# IOTB_EDGE_V3_0.net
KiCad netlist of a schematic drawn in EAGLE
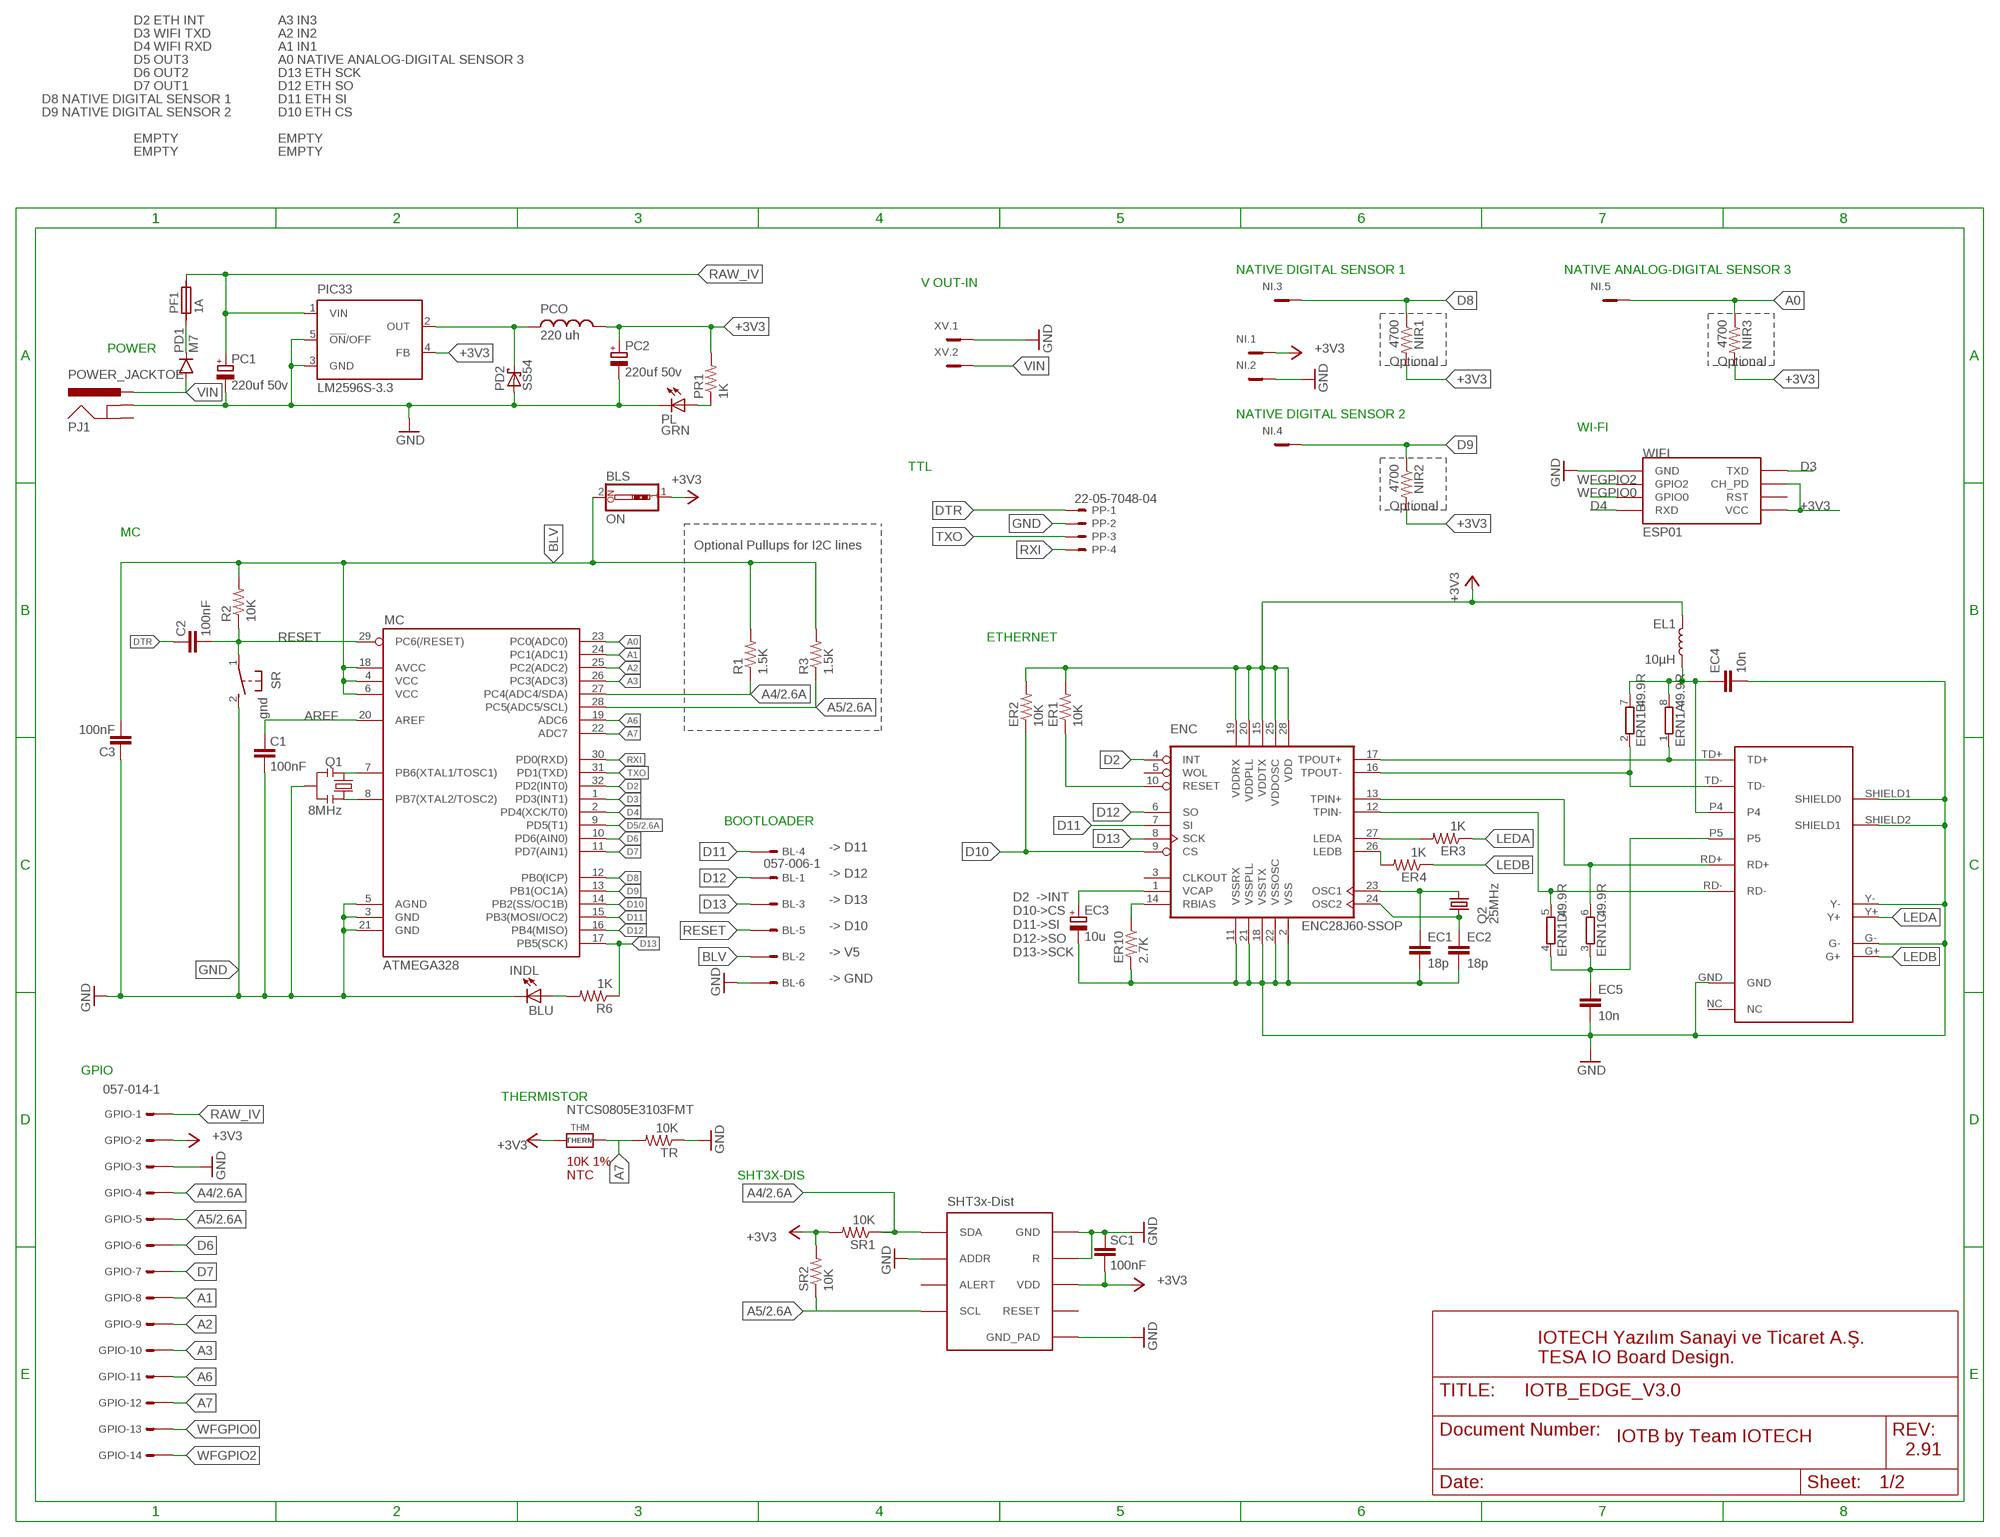
[diagram p0: schematic, sheet 1]
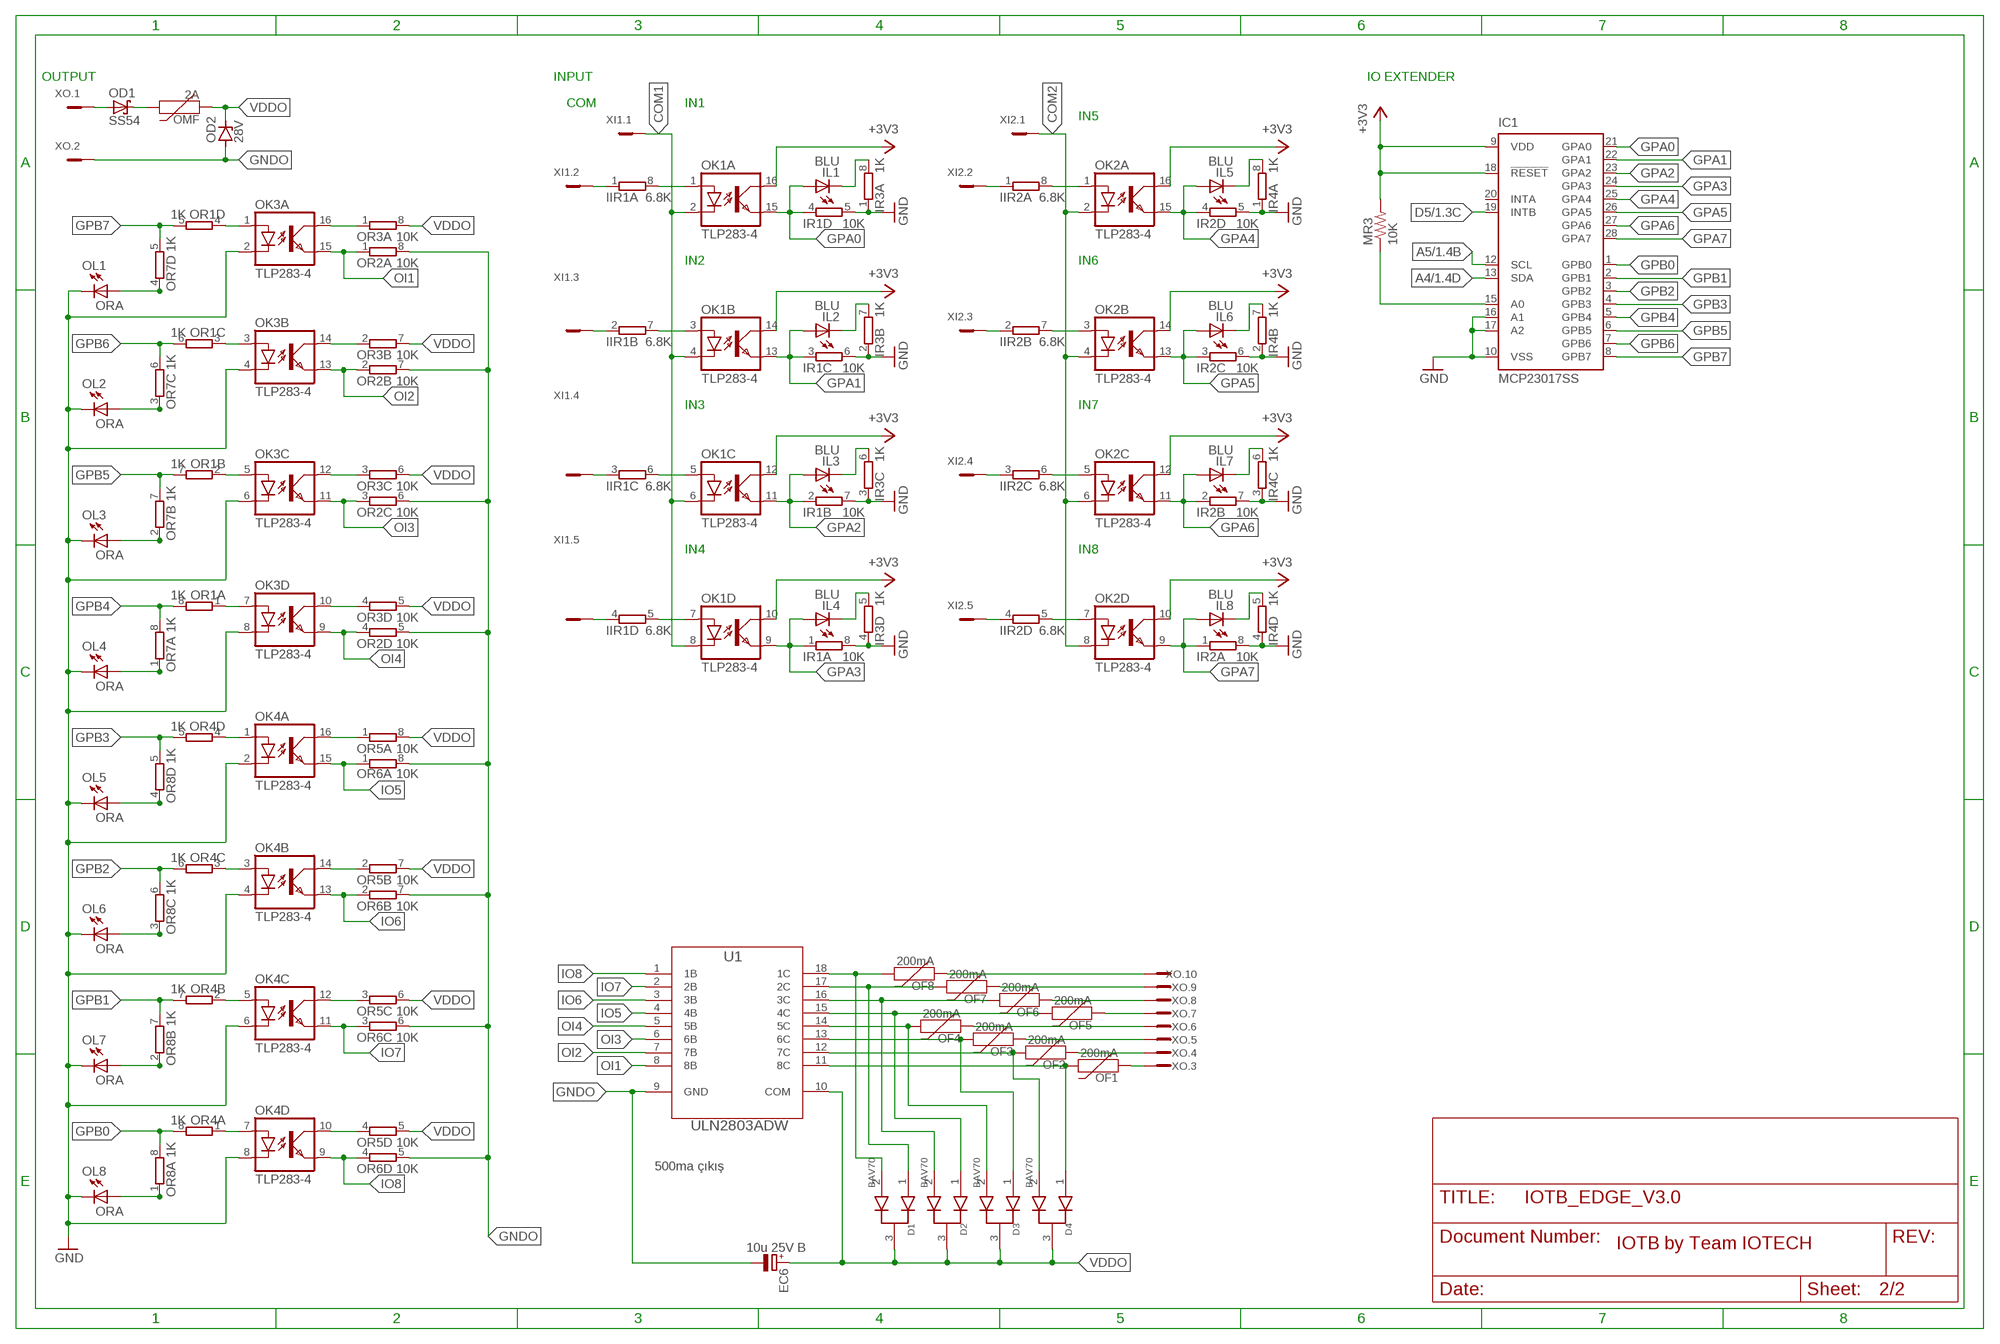
[diagram p1: schematic, sheet 2]

(export (version "E")
  (design (tool "Eeschema 10.0.6"))
  (components
    (comp (ref "D1")
      (value "BAV70")
      (footprint "eagle-import:SOT-23-3")
      (fields (field (name "MF") "Multicomp") (field (name "MP") "BAV70+"))
      (libsource (lib "eagle-import") (part "BAV70"))
    )
    (comp (ref "D2")
      (value "BAV70")
      (footprint "eagle-import:SOT-23-3")
      (fields (field (name "MF") "Multicomp") (field (name "MP") "BAV70+"))
      (libsource (lib "eagle-import") (part "BAV70"))
    )
    (comp (ref "D3")
      (value "BAV70")
      (footprint "eagle-import:SOT-23-3")
      (fields (field (name "MF") "Multicomp") (field (name "MP") "BAV70+"))
      (libsource (lib "eagle-import") (part "BAV70"))
    )
    (comp (ref "D4")
      (value "BAV70")
      (footprint "eagle-import:SOT-23-3")
      (fields (field (name "MF") "Multicomp") (field (name "MP") "BAV70+"))
      (libsource (lib "eagle-import") (part "BAV70"))
    )
    (comp (ref "EC6")
      (value "10u 25V B")
      (footprint "eagle-import:SMC_B")
      (libsource (lib "eagle-import") (part "CPOL-EUSMCB"))
    )
    (comp (ref "IC1")
      (value "MCP23017SS")
      (footprint "eagle-import:SSOP28")
      (fields (field (name "MF") "MICROCHIP") (field (name "MPN") "MCP23017-E/SS"))
      (libsource (lib "eagle-import") (part "MCP23017SS"))
    )
    (comp (ref "IIR1")
      (value "6.8K")
      (footprint "eagle-import:0603-ARV")
      (libsource (lib "eagle-import") (part "4R-N0603-ARV"))
    )
    (comp (ref "IIR2")
      (value "6.8K")
      (footprint "eagle-import:0603-ARV")
      (libsource (lib "eagle-import") (part "4R-N0603-ARV"))
    )
    (comp (ref "IL1")
      (value "BLU")
      (footprint "eagle-import:CHIP-LED0805")
      (libsource (lib "eagle-import") (part "LEDCHIP-LED0805"))
    )
    (comp (ref "IL2")
      (value "BLU")
      (footprint "eagle-import:CHIP-LED0805")
      (libsource (lib "eagle-import") (part "LEDCHIP-LED0805"))
    )
    (comp (ref "IL3")
      (value "BLU")
      (footprint "eagle-import:CHIP-LED0805")
      (libsource (lib "eagle-import") (part "LEDCHIP-LED0805"))
    )
    (comp (ref "IL4")
      (value "BLU")
      (footprint "eagle-import:CHIP-LED0805")
      (libsource (lib "eagle-import") (part "LEDCHIP-LED0805"))
    )
    (comp (ref "IL5")
      (value "BLU")
      (footprint "eagle-import:CHIP-LED0805")
      (libsource (lib "eagle-import") (part "LEDCHIP-LED0805"))
    )
    (comp (ref "IL6")
      (value "BLU")
      (footprint "eagle-import:CHIP-LED0805")
      (libsource (lib "eagle-import") (part "LEDCHIP-LED0805"))
    )
    (comp (ref "IL7")
      (value "BLU")
      (footprint "eagle-import:CHIP-LED0805")
      (libsource (lib "eagle-import") (part "LEDCHIP-LED0805"))
    )
    (comp (ref "IL8")
      (value "BLU")
      (footprint "eagle-import:CHIP-LED0805")
      (libsource (lib "eagle-import") (part "LEDCHIP-LED0805"))
    )
    (comp (ref "IR1")
      (value "10K")
      (footprint "eagle-import:0603-ARV")
      (libsource (lib "eagle-import") (part "4R-N0603-ARV"))
    )
    (comp (ref "IR2")
      (value "10K")
      (footprint "eagle-import:0603-ARV")
      (libsource (lib "eagle-import") (part "4R-N0603-ARV"))
    )
    (comp (ref "IR3")
      (value "1K")
      (footprint "eagle-import:0603-ARV")
      (libsource (lib "eagle-import") (part "4R-N0603-ARV"))
    )
    (comp (ref "IR4")
      (value "1K")
      (footprint "eagle-import:0603-ARV")
      (libsource (lib "eagle-import") (part "4R-N0603-ARV"))
    )
    (comp (ref "MR3")
      (value "10K")
      (footprint "eagle-import:0805")
      (libsource (lib "eagle-import") (part "RESISTOR0805-RES"))
    )
    (comp (ref "OD1")
      (value "SS54")
      (footprint "eagle-import:SMB")
      (libsource (lib "eagle-import") (part "SCHOTTKY-DIODESMD"))
    )
    (comp (ref "OD2")
      (value "28V")
      (footprint "eagle-import:SMB")
      (libsource (lib "eagle-import") (part "ZENER-DIODESMB"))
    )
    (comp (ref "OF1")
      (value "200mA")
      (footprint "eagle-import:1206")
      (libsource (lib "eagle-import") (part "PPTC_0.75A"))
    )
    (comp (ref "OF2")
      (value "200mA")
      (footprint "eagle-import:1206")
      (libsource (lib "eagle-import") (part "PPTC_0.75A"))
    )
    (comp (ref "OF3")
      (value "200mA")
      (footprint "eagle-import:1206")
      (libsource (lib "eagle-import") (part "PPTC_0.75A"))
    )
    (comp (ref "OF4")
      (value "200mA")
      (footprint "eagle-import:1206")
      (libsource (lib "eagle-import") (part "PPTC_0.75A"))
    )
    (comp (ref "OF5")
      (value "200mA")
      (footprint "eagle-import:1206")
      (libsource (lib "eagle-import") (part "PPTC_0.75A"))
    )
    (comp (ref "OF6")
      (value "200mA")
      (footprint "eagle-import:1206")
      (libsource (lib "eagle-import") (part "PPTC_0.75A"))
    )
    (comp (ref "OF7")
      (value "200mA")
      (footprint "eagle-import:1206")
      (libsource (lib "eagle-import") (part "PPTC_0.75A"))
    )
    (comp (ref "OF8")
      (value "200mA")
      (footprint "eagle-import:1206")
      (libsource (lib "eagle-import") (part "PPTC_0.75A"))
    )
    (comp (ref "OK1")
      (value "TLP283-4")
      (footprint "eagle-import:MINI-FLAT-16")
      (fields (field (name "SPICEPREFIX") "O"))
      (libsource (lib "eagle-import") (part "TLP283-4"))
    )
    (comp (ref "OK2")
      (value "TLP283-4")
      (footprint "eagle-import:MINI-FLAT-16")
      (fields (field (name "SPICEPREFIX") "O"))
      (libsource (lib "eagle-import") (part "TLP283-4"))
    )
    (comp (ref "OK3")
      (value "TLP283-4")
      (footprint "eagle-import:MINI-FLAT-16")
      (libsource (lib "eagle-import") (part "TLP283-4"))
    )
    (comp (ref "OK4")
      (value "TLP283-4")
      (footprint "eagle-import:MINI-FLAT-16")
      (libsource (lib "eagle-import") (part "TLP283-4"))
    )
    (comp (ref "OL1")
      (value "ORA")
      (footprint "eagle-import:CHIP-LED0805")
      (libsource (lib "eagle-import") (part "LEDCHIP-LED0805"))
    )
    (comp (ref "OL2")
      (value "ORA")
      (footprint "eagle-import:CHIP-LED0805")
      (libsource (lib "eagle-import") (part "LEDCHIP-LED0805"))
    )
    (comp (ref "OL3")
      (value "ORA")
      (footprint "eagle-import:CHIP-LED0805")
      (libsource (lib "eagle-import") (part "LEDCHIP-LED0805"))
    )
    (comp (ref "OL4")
      (value "ORA")
      (footprint "eagle-import:CHIP-LED0805")
      (libsource (lib "eagle-import") (part "LEDCHIP-LED0805"))
    )
    (comp (ref "OL5")
      (value "ORA")
      (footprint "eagle-import:CHIP-LED0805")
      (libsource (lib "eagle-import") (part "LEDCHIP-LED0805"))
    )
    (comp (ref "OL6")
      (value "ORA")
      (footprint "eagle-import:CHIP-LED0805")
      (libsource (lib "eagle-import") (part "LEDCHIP-LED0805"))
    )
    (comp (ref "OL7")
      (value "ORA")
      (footprint "eagle-import:CHIP-LED0805")
      (libsource (lib "eagle-import") (part "LEDCHIP-LED0805"))
    )
    (comp (ref "OL8")
      (value "ORA")
      (footprint "eagle-import:CHIP-LED0805")
      (libsource (lib "eagle-import") (part "LEDCHIP-LED0805"))
    )
    (comp (ref "OMF")
      (value "2A")
      (footprint "eagle-import:1206")
      (libsource (lib "eagle-import") (part "PPTC_0.75A"))
    )
    (comp (ref "OR1")
      (value "1K")
      (footprint "eagle-import:0603-ARV")
      (libsource (lib "eagle-import") (part "4R-N0603-ARV"))
    )
    (comp (ref "OR2")
      (value "10K")
      (footprint "eagle-import:0603-ARV")
      (libsource (lib "eagle-import") (part "4R-N0603-ARV"))
    )
    (comp (ref "OR3")
      (value "10K")
      (footprint "eagle-import:0603-ARV")
      (libsource (lib "eagle-import") (part "4R-N0603-ARV"))
    )
    (comp (ref "OR4")
      (value "1K")
      (footprint "eagle-import:0603-ARV")
      (libsource (lib "eagle-import") (part "4R-N0603-ARV"))
    )
    (comp (ref "OR5")
      (value "10K")
      (footprint "eagle-import:0603-ARV")
      (libsource (lib "eagle-import") (part "4R-N0603-ARV"))
    )
    (comp (ref "OR6")
      (value "10K")
      (footprint "eagle-import:0603-ARV")
      (libsource (lib "eagle-import") (part "4R-N0603-ARV"))
    )
    (comp (ref "OR7")
      (value "1K")
      (footprint "eagle-import:0603-ARV")
      (libsource (lib "eagle-import") (part "4R-N0603-ARV"))
    )
    (comp (ref "OR8")
      (value "1K")
      (footprint "eagle-import:0603-ARV")
      (libsource (lib "eagle-import") (part "4R-N0603-ARV"))
    )
    (comp (ref "U1")
      (value "ULN2803ADW")
      (footprint "eagle-import:SOIC127P1030X265-18N")
      (libsource (lib "eagle-import") (part "ULN2803ADW"))
    )
    (comp (ref "XI1")
      (value "MC5")
      (footprint "eagle-import:MC5")
      (libsource (lib "eagle-import") (part "MC5"))
    )
    (comp (ref "XI2")
      (value "MC5")
      (footprint "eagle-import:MC5")
      (libsource (lib "eagle-import") (part "MC5"))
    )
    (comp (ref "XO")
      (value "MC10")
      (footprint "eagle-import:MC10")
      (libsource (lib "eagle-import") (part "MC10"))
    )
    (comp (ref "BL")
      (value "057-006-1")
      (footprint "eagle-import:057-006-1")
      (libsource (lib "eagle-import") (part "057-006-1"))
    )
    (comp (ref "BLS")
      (value "ON")
      (footprint "eagle-import:EDG-01")
      (libsource (lib "eagle-import") (part "SW_DIP-1"))
    )
    (comp (ref "C1")
      (value "100nF")
      (footprint "eagle-import:0805")
      (libsource (lib "eagle-import") (part "CAP0805"))
    )
    (comp (ref "C2")
      (value "100nF")
      (footprint "eagle-import:0805")
      (libsource (lib "eagle-import") (part "CAP0805"))
    )
    (comp (ref "C3")
      (value "100nF")
      (footprint "eagle-import:0805")
      (libsource (lib "eagle-import") (part "CAP0805"))
    )
    (comp (ref "EC1")
      (value "18p")
      (footprint "eagle-import:0805")
      (libsource (lib "eagle-import") (part "CAP0805"))
    )
    (comp (ref "EC2")
      (value "18p")
      (footprint "eagle-import:0805")
      (libsource (lib "eagle-import") (part "CAP0805"))
    )
    (comp (ref "EC3")
      (value "10u")
      (footprint "eagle-import:CT3216")
      (libsource (lib "eagle-import") (part "CPOL-EUCT3216"))
    )
    (comp (ref "EC4")
      (value "10n")
      (footprint "eagle-import:0805")
      (libsource (lib "eagle-import") (part "CAP0805"))
    )
    (comp (ref "EC5")
      (value "10n")
      (footprint "eagle-import:0805")
      (libsource (lib "eagle-import") (part "CAP0805"))
    )
    (comp (ref "EL1")
      (value "10µH")
      (footprint "eagle-import:0805")
      (libsource (lib "eagle-import") (part "INDUCTOR-0805-3.3UH"))
    )
    (comp (ref "ENC")
      (value "ENC28J60-SSOP")
      (footprint "eagle-import:SSOP28")
      (libsource (lib "eagle-import") (part "ENC28J60-SSOP"))
    )
    (comp (ref "ER1")
      (value "10K")
      (footprint "eagle-import:0805")
      (libsource (lib "eagle-import") (part "RESISTOR0805-RES"))
    )
    (comp (ref "ER2")
      (value "10K")
      (footprint "eagle-import:0805")
      (libsource (lib "eagle-import") (part "RESISTOR0805-RES"))
    )
    (comp (ref "ER3")
      (value "1K")
      (footprint "eagle-import:0805")
      (libsource (lib "eagle-import") (part "RESISTOR0805-RES"))
    )
    (comp (ref "ER4")
      (value "1K")
      (footprint "eagle-import:0805")
      (libsource (lib "eagle-import") (part "RESISTOR0805-RES"))
    )
    (comp (ref "ER10")
      (value "2.7K")
      (footprint "eagle-import:0805")
      (libsource (lib "eagle-import") (part "RESISTOR0805-RES"))
    )
    (comp (ref "ERN1")
      (value "49.9R")
      (footprint "eagle-import:0603-ARV")
      (libsource (lib "eagle-import") (part "4R-N0603-ARV"))
    )
    (comp (ref "ETHSOC")
      (value "HR911105A")
      (footprint "eagle-import:RJ45")
      (libsource (lib "eagle-import") (part "HR911105A"))
    )
    (comp (ref "GPIO")
      (value "057-014-1")
      (footprint "eagle-import:057-014-1")
      (libsource (lib "eagle-import") (part "057-014-1"))
    )
    (comp (ref "INDL")
      (value "BLU")
      (footprint "eagle-import:CHIP-LED0805")
      (libsource (lib "eagle-import") (part "LEDCHIP-LED0805"))
    )
    (comp (ref "MC")
      (value "ATMEGA328")
      (footprint "eagle-import:TQFP32-08")
      (libsource (lib "eagle-import") (part "ATMEGA168"))
    )
    (comp (ref "NI")
      (value "MC5")
      (footprint "eagle-import:MC5")
      (libsource (lib "eagle-import") (part "MC5"))
    )
    (comp (ref "NIR1")
      (value "4700")
      (footprint "eagle-import:0805")
      (libsource (lib "eagle-import") (part "RESISTOR0805-RES"))
    )
    (comp (ref "NIR2")
      (value "4700")
      (footprint "eagle-import:0805")
      (libsource (lib "eagle-import") (part "RESISTOR0805-RES"))
    )
    (comp (ref "NIR3")
      (value "4700")
      (footprint "eagle-import:0805")
      (libsource (lib "eagle-import") (part "RESISTOR0805-RES"))
    )
    (comp (ref "PC1")
      (value "220uf 50v")
      (footprint "eagle-import:140CLH-1010")
      (libsource (lib "eagle-import") (part "CPOL-EU140CLH-1010"))
    )
    (comp (ref "PC2")
      (value "220uf 50v")
      (footprint "eagle-import:140CLH-1010")
      (libsource (lib "eagle-import") (part "CPOL-EU140CLH-1010"))
    )
    (comp (ref "PCO")
      (value "220 uh")
      (footprint "eagle-import:MSS1260")
      (libsource (lib "eagle-import") (part "MSS1260"))
    )
    (comp (ref "PD1")
      (value "M7")
      (footprint "eagle-import:SMA-DIODE")
      (libsource (lib "eagle-import") (part "DIODESMA"))
    )
    (comp (ref "PD2")
      (value "SS54")
      (footprint "eagle-import:SMB")
      (libsource (lib "eagle-import") (part "SCHOTTKY-DIODESMD"))
    )
    (comp (ref "PF1")
      (value "1A")
      (footprint "eagle-import:1820")
      (libsource (lib "eagle-import") (part "SIBA194600"))
    )
    (comp (ref "PIC33")
      (value "LM2596S-3.3")
      (footprint "eagle-import:TO263-5")
      (fields
        (field (name "MF") "NATIONAL SEMICONDUCTOR")
        (field (name "MPN") "LM2596S-ADJ/NOPB")
        (field (name "SPICEPREFIX") "X")
      )
      (libsource (lib "eagle-import") (part "LM2596S"))
    )
    (comp (ref "PJ1")
      (value "POWER_JACKTOE")
      (footprint "eagle-import:POWER_JACK_SMD_OVERPASTE_TOE")
      (libsource (lib "eagle-import") (part "POWER_JACKTOE"))
    )
    (comp (ref "PL")
      (value "GRN")
      (footprint "eagle-import:CHIP-LED0805")
      (libsource (lib "eagle-import") (part "LEDCHIP-LED0805"))
    )
    (comp (ref "PP")
      (value "22-05-7048-04")
      (footprint "eagle-import:7395-04")
      (fields (field (name "MF") "MOLEX"))
      (libsource (lib "eagle-import") (part "22-?-0405-7048"))
    )
    (comp (ref "PR1")
      (value "1K")
      (footprint "eagle-import:0805")
      (libsource (lib "eagle-import") (part "RESISTOR0805-RES"))
    )
    (comp (ref "Q1")
      (value "8MHz")
      (footprint "eagle-import:RESONATOR-SMD-1_1")
      (libsource (lib "eagle-import") (part "RESONATOR1{colon}1"))
    )
    (comp (ref "Q2")
      (value "25MHz")
      (footprint "eagle-import:5.0X3.2_2")
      (libsource (lib "eagle-import") (part "KX-9B"))
    )
    (comp (ref "R1")
      (value "1.5K")
      (footprint "eagle-import:0805")
      (libsource (lib "eagle-import") (part "RESISTOR0805-RES"))
    )
    (comp (ref "R2")
      (value "10K")
      (footprint "eagle-import:0805")
      (libsource (lib "eagle-import") (part "RESISTOR0805-RES"))
    )
    (comp (ref "R3")
      (value "1.5K")
      (footprint "eagle-import:0805")
      (libsource (lib "eagle-import") (part "RESISTOR0805-RES"))
    )
    (comp (ref "R6")
      (value "1K")
      (footprint "eagle-import:0805")
      (libsource (lib "eagle-import") (part "RESISTOR0805-RES"))
    )
    (comp (ref "SC1")
      (value "100nF")
      (footprint "eagle-import:0805")
      (libsource (lib "eagle-import") (part "CAP0805"))
    )
    (comp (ref "SHT")
      (value "SHT3X")
      (footprint "eagle-import:SHT3X")
      (libsource (lib "eagle-import") (part "SHT3X"))
    )
    (comp (ref "SR")
      (value "gnd")
      (footprint "eagle-import:B3F-31XX")
      (fields (field (name "MPN") "B3F-3100"))
      (libsource (lib "eagle-import") (part "31-XX"))
    )
    (comp (ref "SR1")
      (value "10K")
      (footprint "eagle-import:0805")
      (libsource (lib "eagle-import") (part "RESISTOR0805-RES"))
    )
    (comp (ref "SR2")
      (value "10K")
      (footprint "eagle-import:0805")
      (libsource (lib "eagle-import") (part "RESISTOR0805-RES"))
    )
    (comp (ref "THM")
      (value "THERM")
      (footprint "eagle-import:MICROBUILDER_0805_NOTHERMALS")
      (libsource (lib "eagle-import") (part "MICROBUILDER_RESISTOR0805_NOTHERMALS"))
    )
    (comp (ref "TR")
      (value "10K")
      (footprint "eagle-import:0805")
      (libsource (lib "eagle-import") (part "RESISTOR0805-RES"))
    )
    (comp (ref "WIFI")
      (value "ESP01")
      (footprint "eagle-import:ESP01")
      (libsource (lib "eagle-import") (part "ESP01"))
    )
    (comp (ref "XV")
      (value "MC2")
      (footprint "eagle-import:MC2")
      (libsource (lib "eagle-import") (part "MC2"))
    )
  )
  (nets
    (net (code "1") (name "+3V3") (class "Default")
      (node (ref "BLS") (pin "1") (pinfunction "1_1") (pintype "passive"))
      (node (ref "EL1") (pin "1") (pinfunction "1_1") (pintype "passive"))
      (node (ref "ENC") (pin "15") (pinfunction "VDDTX_15") (pintype "power_in"))
      (node (ref "ENC") (pin "19") (pinfunction "VDDRX_19") (pintype "power_in"))
      (node (ref "ENC") (pin "20") (pinfunction "VDDPLL_20") (pintype "power_in"))
      (node (ref "ENC") (pin "25") (pinfunction "VDDOSC_25") (pintype "power_in"))
      (node (ref "ENC") (pin "28") (pinfunction "VDD_28") (pintype "power_in"))
      (node (ref "ER1") (pin "2") (pinfunction "2_2") (pintype "passive"))
      (node (ref "ER2") (pin "2") (pinfunction "2_2") (pintype "passive"))
      (node (ref "GPIO") (pin "2") (pinfunction "S_2") (pintype "passive"))
      (node (ref "IC1") (pin "18") (pinfunction "~{RESET}_18") (pintype "input"))
      (node (ref "IC1") (pin "9") (pinfunction "VDD_9") (pintype "power_in"))
      (node (ref "MR3") (pin "2") (pinfunction "2_2") (pintype "passive"))
      (node (ref "NI") (pin "1") (pinfunction "SK_1") (pintype "passive"))
      (node (ref "NIR1") (pin "2") (pinfunction "2_2") (pintype "passive"))
      (node (ref "NIR2") (pin "2") (pinfunction "2_2") (pintype "passive"))
      (node (ref "NIR3") (pin "2") (pinfunction "2_2") (pintype "passive"))
      (node (ref "OK1") (pin "10") (pinfunction "COL_10") (pintype "passive"))
      (node (ref "OK1") (pin "12") (pinfunction "COL_12") (pintype "passive"))
      (node (ref "OK1") (pin "14") (pinfunction "COL_14") (pintype "passive"))
      (node (ref "OK1") (pin "16") (pinfunction "COL_16") (pintype "passive"))
      (node (ref "OK2") (pin "10") (pinfunction "COL_10") (pintype "passive"))
      (node (ref "OK2") (pin "12") (pinfunction "COL_12") (pintype "passive"))
      (node (ref "OK2") (pin "14") (pinfunction "COL_14") (pintype "passive"))
      (node (ref "OK2") (pin "16") (pinfunction "COL_16") (pintype "passive"))
      (node (ref "PC2") (pin "+") (pinfunction "+_+") (pintype "passive"))
      (node (ref "PCO") (pin "P$1") (pinfunction "P$1_P$1") (pintype "passive"))
      (node (ref "PIC33") (pin "4") (pinfunction "FB_4") (pintype "input"))
      (node (ref "PR1") (pin "2") (pinfunction "2_2") (pintype "passive"))
      (node (ref "SC1") (pin "1") (pinfunction "1_1") (pintype "passive"))
      (node (ref "SHT") (pin "VDD") (pinfunction "VDD_VDD") (pintype "bidirectional"))
      (node (ref "SR1") (pin "2") (pinfunction "2_2") (pintype "passive"))
      (node (ref "SR2") (pin "2") (pinfunction "2_2") (pintype "passive"))
      (node (ref "THM") (pin "1") (pinfunction "1_1") (pintype "passive"))
      (node (ref "WIFI") (pin "CH_PD") (pinfunction "CH_PD_CH_PD") (pintype "bidirectional"))
      (node (ref "WIFI") (pin "VCC") (pinfunction "VCC_VCC") (pintype "bidirectional"))
    )
    (net (code "2") (name "A0") (class "Default")
      (node (ref "MC") (pin "23") (pinfunction "PC0(ADC0)_23") (pintype "bidirectional"))
      (node (ref "NI") (pin "5") (pinfunction "SK_5") (pintype "passive"))
      (node (ref "NIR3") (pin "1") (pinfunction "1_1") (pintype "passive"))
    )
    (net (code "3") (name "A1") (class "Default")
      (node (ref "GPIO") (pin "8") (pinfunction "S_8") (pintype "passive"))
      (node (ref "MC") (pin "24") (pinfunction "PC1(ADC1)_24") (pintype "bidirectional"))
    )
    (net (code "4") (name "A2") (class "Default")
      (node (ref "GPIO") (pin "9") (pinfunction "S_9") (pintype "passive"))
      (node (ref "MC") (pin "25") (pinfunction "PC2(ADC2)_25") (pintype "bidirectional"))
    )
    (net (code "5") (name "A3") (class "Default")
      (node (ref "GPIO") (pin "10") (pinfunction "S_10") (pintype "passive"))
      (node (ref "MC") (pin "26") (pinfunction "PC3(ADC3)_26") (pintype "bidirectional"))
    )
    (net (code "6") (name "A4") (class "Default")
      (node (ref "GPIO") (pin "4") (pinfunction "S_4") (pintype "passive"))
      (node (ref "IC1") (pin "13") (pinfunction "SDA_13") (pintype "bidirectional"))
      (node (ref "MC") (pin "27") (pinfunction "PC4(ADC4/SDA)_27") (pintype "bidirectional"))
      (node (ref "R1") (pin "1") (pinfunction "1_1") (pintype "passive"))
      (node (ref "SHT") (pin "SDA") (pinfunction "SDA_SDA") (pintype "bidirectional"))
      (node (ref "SR1") (pin "1") (pinfunction "1_1") (pintype "passive"))
    )
    (net (code "7") (name "A5") (class "Default")
      (node (ref "GPIO") (pin "5") (pinfunction "S_5") (pintype "passive"))
      (node (ref "IC1") (pin "12") (pinfunction "SCL_12") (pintype "input"))
      (node (ref "MC") (pin "28") (pinfunction "PC5(ADC5/SCL)_28") (pintype "bidirectional"))
      (node (ref "R3") (pin "1") (pinfunction "1_1") (pintype "passive"))
      (node (ref "SHT") (pin "SCL") (pinfunction "SCL_SCL") (pintype "bidirectional"))
      (node (ref "SR2") (pin "1") (pinfunction "1_1") (pintype "passive"))
    )
    (net (code "8") (name "A6") (class "Default")
      (node (ref "GPIO") (pin "11") (pinfunction "S_11") (pintype "passive"))
      (node (ref "MC") (pin "19") (pinfunction "ADC6_19") (pintype "bidirectional"))
    )
    (net (code "9") (name "A7") (class "Default")
      (node (ref "GPIO") (pin "12") (pinfunction "S_12") (pintype "passive"))
      (node (ref "MC") (pin "22") (pinfunction "ADC7_22") (pintype "bidirectional"))
      (node (ref "THM") (pin "2") (pinfunction "2_2") (pintype "passive"))
      (node (ref "TR") (pin "2") (pinfunction "2_2") (pintype "passive"))
    )
    (net (code "10") (name "AREF") (class "Default")
      (node (ref "C1") (pin "2") (pinfunction "2_2") (pintype "passive"))
      (node (ref "MC") (pin "20") (pinfunction "AREF_20") (pintype "bidirectional"))
    )
    (net (code "11") (name "BLV") (class "Default")
      (node (ref "BL") (pin "2") (pinfunction "S_2") (pintype "passive"))
      (node (ref "BLS") (pin "2") (pinfunction "2_2") (pintype "passive"))
      (node (ref "C3") (pin "1") (pinfunction "1_1") (pintype "passive"))
      (node (ref "MC") (pin "18") (pinfunction "AVCC_18") (pintype "bidirectional"))
      (node (ref "MC") (pin "4") (pinfunction "VCC_4") (pintype "bidirectional"))
      (node (ref "MC") (pin "6") (pinfunction "VCC_6") (pintype "bidirectional"))
      (node (ref "R1") (pin "2") (pinfunction "2_2") (pintype "passive"))
      (node (ref "R2") (pin "2") (pinfunction "2_2") (pintype "passive"))
      (node (ref "R3") (pin "2") (pinfunction "2_2") (pintype "passive"))
    )
    (net (code "12") (name "COM1") (class "Default")
      (node (ref "OK1") (pin "2") (pinfunction "C_2") (pintype "passive"))
      (node (ref "OK1") (pin "4") (pinfunction "C_4") (pintype "passive"))
      (node (ref "OK1") (pin "6") (pinfunction "C_6") (pintype "passive"))
      (node (ref "OK1") (pin "8") (pinfunction "C_8") (pintype "passive"))
      (node (ref "XI1") (pin "1") (pinfunction "SK_1") (pintype "passive"))
    )
    (net (code "13") (name "COM2") (class "Default")
      (node (ref "OK2") (pin "2") (pinfunction "C_2") (pintype "passive"))
      (node (ref "OK2") (pin "4") (pinfunction "C_4") (pintype "passive"))
      (node (ref "OK2") (pin "6") (pinfunction "C_6") (pintype "passive"))
      (node (ref "OK2") (pin "8") (pinfunction "C_8") (pintype "passive"))
      (node (ref "XI2") (pin "1") (pinfunction "SK_1") (pintype "passive"))
    )
    (net (code "14") (name "D2") (class "Default")
      (node (ref "ENC") (pin "4") (pinfunction "INT_4") (pintype "output"))
      (node (ref "MC") (pin "32") (pinfunction "PD2(INT0)_32") (pintype "bidirectional"))
    )
    (net (code "15") (name "D3") (class "Default")
      (node (ref "MC") (pin "1") (pinfunction "PD3(INT1)_1") (pintype "bidirectional"))
      (node (ref "WIFI") (pin "TX") (pinfunction "TXD_TX") (pintype "bidirectional"))
    )
    (net (code "16") (name "D4") (class "Default")
      (node (ref "MC") (pin "2") (pinfunction "PD4(XCK/T0)_2") (pintype "bidirectional"))
      (node (ref "WIFI") (pin "RX") (pinfunction "RXD_RX") (pintype "bidirectional"))
    )
    (net (code "17") (name "D5") (class "Default")
      (node (ref "IC1") (pin "19") (pinfunction "INTB_19") (pintype "output"))
      (node (ref "MC") (pin "9") (pinfunction "PD5(T1)_9") (pintype "bidirectional"))
    )
    (net (code "18") (name "D6") (class "Default")
      (node (ref "GPIO") (pin "6") (pinfunction "S_6") (pintype "passive"))
      (node (ref "MC") (pin "10") (pinfunction "PD6(AIN0)_10") (pintype "bidirectional"))
    )
    (net (code "19") (name "D7") (class "Default")
      (node (ref "GPIO") (pin "7") (pinfunction "S_7") (pintype "passive"))
      (node (ref "MC") (pin "11") (pinfunction "PD7(AIN1)_11") (pintype "bidirectional"))
    )
    (net (code "20") (name "D8") (class "Default")
      (node (ref "MC") (pin "12") (pinfunction "PB0(ICP)_12") (pintype "bidirectional"))
      (node (ref "NI") (pin "3") (pinfunction "SK_3") (pintype "passive"))
      (node (ref "NIR1") (pin "1") (pinfunction "1_1") (pintype "passive"))
    )
    (net (code "21") (name "D9") (class "Default")
      (node (ref "MC") (pin "13") (pinfunction "PB1(OC1A)_13") (pintype "bidirectional"))
      (node (ref "NI") (pin "4") (pinfunction "SK_4") (pintype "passive"))
      (node (ref "NIR2") (pin "1") (pinfunction "1_1") (pintype "passive"))
    )
    (net (code "22") (name "D10") (class "Default")
      (node (ref "ENC") (pin "9") (pinfunction "CS_9") (pintype "input"))
      (node (ref "ER2") (pin "1") (pinfunction "1_1") (pintype "passive"))
      (node (ref "MC") (pin "14") (pinfunction "PB2(SS/OC1B)_14") (pintype "bidirectional"))
    )
    (net (code "23") (name "D11") (class "Default")
      (node (ref "BL") (pin "4") (pinfunction "S_4") (pintype "passive"))
      (node (ref "ENC") (pin "7") (pinfunction "SI_7") (pintype "input"))
      (node (ref "MC") (pin "15") (pinfunction "PB3(MOSI/OC2)_15") (pintype "bidirectional"))
    )
    (net (code "24") (name "D12") (class "Default")
      (node (ref "BL") (pin "1") (pinfunction "S_1") (pintype "passive"))
      (node (ref "ENC") (pin "6") (pinfunction "SO_6") (pintype "output"))
      (node (ref "MC") (pin "16") (pinfunction "PB4(MISO)_16") (pintype "bidirectional"))
    )
    (net (code "25") (name "D13") (class "Default")
      (node (ref "BL") (pin "3") (pinfunction "S_3") (pintype "passive"))
      (node (ref "ENC") (pin "8") (pinfunction "SCK_8") (pintype "input"))
      (node (ref "MC") (pin "17") (pinfunction "PB5(SCK)_17") (pintype "bidirectional"))
      (node (ref "R6") (pin "1") (pinfunction "1_1") (pintype "passive"))
    )
    (net (code "26") (name "DTR") (class "Default")
      (node (ref "C2") (pin "2") (pinfunction "2_2") (pintype "passive"))
      (node (ref "PP") (pin "1") (pinfunction "S_1") (pintype "passive"))
    )
    (net (code "27") (name "GND") (class "Default")
      (node (ref "BL") (pin "6") (pinfunction "S_6") (pintype "passive"))
      (node (ref "C1") (pin "1") (pinfunction "1_1") (pintype "passive"))
      (node (ref "C3") (pin "2") (pinfunction "2_2") (pintype "passive"))
      (node (ref "EC1") (pin "2") (pinfunction "2_2") (pintype "passive"))
      (node (ref "EC2") (pin "2") (pinfunction "2_2") (pintype "passive"))
      (node (ref "EC3") (pin "-") (pinfunction "-_-") (pintype "passive"))
      (node (ref "EC4") (pin "2") (pinfunction "2_2") (pintype "passive"))
      (node (ref "EC5") (pin "2") (pinfunction "2_2") (pintype "passive"))
      (node (ref "ENC") (pin "11") (pinfunction "VSSRX_11") (pintype "power_in"))
      (node (ref "ENC") (pin "18") (pinfunction "VSSTX_18") (pintype "power_in"))
      (node (ref "ENC") (pin "2") (pinfunction "VSS_2") (pintype "power_in"))
      (node (ref "ENC") (pin "21") (pinfunction "VSSPLL_21") (pintype "power_in"))
      (node (ref "ENC") (pin "22") (pinfunction "VSSOSC_22") (pintype "power_in"))
      (node (ref "ER10") (pin "2") (pinfunction "2_2") (pintype "passive"))
      (node (ref "ETHSOC") (pin "G-") (pinfunction "G-_G-") (pintype "bidirectional"))
      (node (ref "ETHSOC") (pin "GND") (pinfunction "GND_GND") (pintype "bidirectional"))
      (node (ref "ETHSOC") (pin "SHIELD1") (pinfunction "SHIELD0_SHIELD1") (pintype "bidirectional"))
      (node (ref "ETHSOC") (pin "SHIELD2") (pinfunction "SHIELD1_SHIELD2") (pintype "bidirectional"))
      (node (ref "ETHSOC") (pin "Y-") (pinfunction "Y-_Y-") (pintype "bidirectional"))
      (node (ref "GPIO") (pin "3") (pinfunction "S_3") (pintype "passive"))
      (node (ref "IC1") (pin "10") (pinfunction "VSS_10") (pintype "power_in"))
      (node (ref "IC1") (pin "16") (pinfunction "A1_16") (pintype "input"))
      (node (ref "IC1") (pin "17") (pinfunction "A2_17") (pintype "input"))
      (node (ref "INDL") (pin "C") (pinfunction "C_C") (pintype "passive"))
      (node (ref "IR1") (pin "5") (pinfunction "2_5") (pintype "passive"))
      (node (ref "IR1") (pin "6") (pinfunction "2_6") (pintype "passive"))
      (node (ref "IR1") (pin "7") (pinfunction "2_7") (pintype "passive"))
      (node (ref "IR1") (pin "8") (pinfunction "2_8") (pintype "passive"))
      (node (ref "IR2") (pin "5") (pinfunction "2_5") (pintype "passive"))
      (node (ref "IR2") (pin "6") (pinfunction "2_6") (pintype "passive"))
      (node (ref "IR2") (pin "7") (pinfunction "2_7") (pintype "passive"))
      (node (ref "IR2") (pin "8") (pinfunction "2_8") (pintype "passive"))
      (node (ref "IR3") (pin "1") (pinfunction "1_1") (pintype "passive"))
      (node (ref "IR3") (pin "2") (pinfunction "1_2") (pintype "passive"))
      (node (ref "IR3") (pin "3") (pinfunction "1_3") (pintype "passive"))
      (node (ref "IR3") (pin "4") (pinfunction "1_4") (pintype "passive"))
      (node (ref "IR4") (pin "1") (pinfunction "1_1") (pintype "passive"))
      (node (ref "IR4") (pin "2") (pinfunction "1_2") (pintype "passive"))
      (node (ref "IR4") (pin "3") (pinfunction "1_3") (pintype "passive"))
      (node (ref "IR4") (pin "4") (pinfunction "1_4") (pintype "passive"))
      (node (ref "MC") (pin "21") (pinfunction "GND_21") (pintype "bidirectional"))
      (node (ref "MC") (pin "3") (pinfunction "GND_3") (pintype "bidirectional"))
      (node (ref "MC") (pin "5") (pinfunction "AGND_5") (pintype "bidirectional"))
      (node (ref "NI") (pin "2") (pinfunction "SK_2") (pintype "passive"))
      (node (ref "OK3") (pin "2") (pinfunction "C_2") (pintype "passive"))
      (node (ref "OK3") (pin "4") (pinfunction "C_4") (pintype "passive"))
      (node (ref "OK3") (pin "6") (pinfunction "C_6") (pintype "passive"))
      (node (ref "OK3") (pin "8") (pinfunction "C_8") (pintype "passive"))
      (node (ref "OK4") (pin "2") (pinfunction "C_2") (pintype "passive"))
      (node (ref "OK4") (pin "4") (pinfunction "C_4") (pintype "passive"))
      (node (ref "OK4") (pin "6") (pinfunction "C_6") (pintype "passive"))
      (node (ref "OK4") (pin "8") (pinfunction "C_8") (pintype "passive"))
      (node (ref "OL1") (pin "C") (pinfunction "C_C") (pintype "passive"))
      (node (ref "OL2") (pin "C") (pinfunction "C_C") (pintype "passive"))
      (node (ref "OL3") (pin "C") (pinfunction "C_C") (pintype "passive"))
      (node (ref "OL4") (pin "C") (pinfunction "C_C") (pintype "passive"))
      (node (ref "OL5") (pin "C") (pinfunction "C_C") (pintype "passive"))
      (node (ref "OL6") (pin "C") (pinfunction "C_C") (pintype "passive"))
      (node (ref "OL7") (pin "C") (pinfunction "C_C") (pintype "passive"))
      (node (ref "OL8") (pin "C") (pinfunction "C_C") (pintype "passive"))
      (node (ref "PC1") (pin "-") (pinfunction "-_-") (pintype "passive"))
      (node (ref "PC2") (pin "-") (pinfunction "-_-") (pintype "passive"))
      (node (ref "PD2") (pin "A") (pinfunction "A_A") (pintype "passive"))
      (node (ref "PIC33") (pin "3") (pinfunction "GND_3") (pintype "power_in"))
      (node (ref "PIC33") (pin "5") (pinfunction "~{ON}/OFF_5") (pintype "input"))
      (node (ref "PJ1") (pin "GND") (pinfunction "GNDBREAK_GND") (pintype "bidirectional"))
      (node (ref "PL") (pin "C") (pinfunction "C_C") (pintype "passive"))
      (node (ref "PP") (pin "2") (pinfunction "S_2") (pintype "passive"))
      (node (ref "Q1") (pin "2") (pinfunction "2_2") (pintype "passive"))
      (node (ref "SC1") (pin "2") (pinfunction "2_2") (pintype "passive"))
      (node (ref "SHT") (pin "ADDR") (pinfunction "ADDR_ADDR") (pintype "bidirectional"))
      (node (ref "SHT") (pin "GND") (pinfunction "GND_GND") (pintype "bidirectional"))
      (node (ref "SHT") (pin "GND_PAD") (pinfunction "GND_PAD_GND_PAD") (pintype "bidirectional"))
      (node (ref "SHT") (pin "R") (pinfunction "R_R") (pintype "bidirectional"))
      (node (ref "SR") (pin "2") (pinfunction "S_2") (pintype "passive"))
      (node (ref "TR") (pin "1") (pinfunction "1_1") (pintype "passive"))
      (node (ref "WIFI") (pin "GND") (pinfunction "GND_GND") (pintype "bidirectional"))
      (node (ref "XV") (pin "1") (pinfunction "SK_1") (pintype "passive"))
    )
    (net (code "28") (name "GNDO") (class "Default")
      (node (ref "EC6") (pin "-") (pinfunction "-_-") (pintype "passive"))
      (node (ref "OD2") (pin "A") (pinfunction "A_A") (pintype "passive"))
      (node (ref "OR2") (pin "5") (pinfunction "2_5") (pintype "passive"))
      (node (ref "OR2") (pin "6") (pinfunction "2_6") (pintype "passive"))
      (node (ref "OR2") (pin "7") (pinfunction "2_7") (pintype "passive"))
      (node (ref "OR2") (pin "8") (pinfunction "2_8") (pintype "passive"))
      (node (ref "OR6") (pin "5") (pinfunction "2_5") (pintype "passive"))
      (node (ref "OR6") (pin "6") (pinfunction "2_6") (pintype "passive"))
      (node (ref "OR6") (pin "7") (pinfunction "2_7") (pintype "passive"))
      (node (ref "OR6") (pin "8") (pinfunction "2_8") (pintype "passive"))
      (node (ref "U1") (pin "9") (pinfunction "GND_9") (pintype "passive"))
      (node (ref "XO") (pin "2") (pinfunction "SK_2") (pintype "passive"))
    )
    (net (code "29") (name "GPA0") (class "Default")
      (node (ref "IC1") (pin "21") (pinfunction "GPA0_21") (pintype "bidirectional"))
      (node (ref "IL1") (pin "A") (pinfunction "A_A") (pintype "passive"))
      (node (ref "IR1") (pin "4") (pinfunction "1_4") (pintype "passive"))
      (node (ref "OK1") (pin "15") (pinfunction "EMIT_15") (pintype "passive"))
    )
    (net (code "30") (name "GPA1") (class "Default")
      (node (ref "IC1") (pin "22") (pinfunction "GPA1_22") (pintype "bidirectional"))
      (node (ref "IL2") (pin "A") (pinfunction "A_A") (pintype "passive"))
      (node (ref "IR1") (pin "3") (pinfunction "1_3") (pintype "passive"))
      (node (ref "OK1") (pin "13") (pinfunction "EMIT_13") (pintype "passive"))
    )
    (net (code "31") (name "GPA2") (class "Default")
      (node (ref "IC1") (pin "23") (pinfunction "GPA2_23") (pintype "bidirectional"))
      (node (ref "IL3") (pin "A") (pinfunction "A_A") (pintype "passive"))
      (node (ref "IR1") (pin "2") (pinfunction "1_2") (pintype "passive"))
      (node (ref "OK1") (pin "11") (pinfunction "EMIT_11") (pintype "passive"))
    )
    (net (code "32") (name "GPA3") (class "Default")
      (node (ref "IC1") (pin "24") (pinfunction "GPA3_24") (pintype "bidirectional"))
      (node (ref "IL4") (pin "A") (pinfunction "A_A") (pintype "passive"))
      (node (ref "IR1") (pin "1") (pinfunction "1_1") (pintype "passive"))
      (node (ref "OK1") (pin "9") (pinfunction "EMIT_9") (pintype "passive"))
    )
    (net (code "33") (name "GPA4") (class "Default")
      (node (ref "IC1") (pin "25") (pinfunction "GPA4_25") (pintype "bidirectional"))
      (node (ref "IL5") (pin "A") (pinfunction "A_A") (pintype "passive"))
      (node (ref "IR2") (pin "4") (pinfunction "1_4") (pintype "passive"))
      (node (ref "OK2") (pin "15") (pinfunction "EMIT_15") (pintype "passive"))
    )
    (net (code "34") (name "GPA5") (class "Default")
      (node (ref "IC1") (pin "26") (pinfunction "GPA5_26") (pintype "bidirectional"))
      (node (ref "IL6") (pin "A") (pinfunction "A_A") (pintype "passive"))
      (node (ref "IR2") (pin "3") (pinfunction "1_3") (pintype "passive"))
      (node (ref "OK2") (pin "13") (pinfunction "EMIT_13") (pintype "passive"))
    )
    (net (code "35") (name "GPA6") (class "Default")
      (node (ref "IC1") (pin "27") (pinfunction "GPA6_27") (pintype "bidirectional"))
      (node (ref "IL7") (pin "A") (pinfunction "A_A") (pintype "passive"))
      (node (ref "IR2") (pin "2") (pinfunction "1_2") (pintype "passive"))
      (node (ref "OK2") (pin "11") (pinfunction "EMIT_11") (pintype "passive"))
    )
    (net (code "36") (name "GPA7") (class "Default")
      (node (ref "IC1") (pin "28") (pinfunction "GPA7_28") (pintype "bidirectional"))
      (node (ref "IL8") (pin "A") (pinfunction "A_A") (pintype "passive"))
      (node (ref "IR2") (pin "1") (pinfunction "1_1") (pintype "passive"))
      (node (ref "OK2") (pin "9") (pinfunction "EMIT_9") (pintype "passive"))
    )
    (net (code "37") (name "GPB0") (class "Default")
      (node (ref "IC1") (pin "1") (pinfunction "GPB0_1") (pintype "bidirectional"))
      (node (ref "OR4") (pin "8") (pinfunction "2_8") (pintype "passive"))
      (node (ref "OR8") (pin "8") (pinfunction "2_8") (pintype "passive"))
    )
    (net (code "38") (name "GPB1") (class "Default")
      (node (ref "IC1") (pin "2") (pinfunction "GPB1_2") (pintype "bidirectional"))
      (node (ref "OR4") (pin "7") (pinfunction "2_7") (pintype "passive"))
      (node (ref "OR8") (pin "7") (pinfunction "2_7") (pintype "passive"))
    )
    (net (code "39") (name "GPB2") (class "Default")
      (node (ref "IC1") (pin "3") (pinfunction "GPB2_3") (pintype "bidirectional"))
      (node (ref "OR4") (pin "6") (pinfunction "2_6") (pintype "passive"))
      (node (ref "OR8") (pin "6") (pinfunction "2_6") (pintype "passive"))
    )
    (net (code "40") (name "GPB3") (class "Default")
      (node (ref "IC1") (pin "4") (pinfunction "GPB3_4") (pintype "bidirectional"))
      (node (ref "OR4") (pin "5") (pinfunction "2_5") (pintype "passive"))
      (node (ref "OR8") (pin "5") (pinfunction "2_5") (pintype "passive"))
    )
    (net (code "41") (name "GPB4") (class "Default")
      (node (ref "IC1") (pin "5") (pinfunction "GPB4_5") (pintype "bidirectional"))
      (node (ref "OR1") (pin "8") (pinfunction "2_8") (pintype "passive"))
      (node (ref "OR7") (pin "8") (pinfunction "2_8") (pintype "passive"))
    )
    (net (code "42") (name "GPB5") (class "Default")
      (node (ref "IC1") (pin "6") (pinfunction "GPB5_6") (pintype "bidirectional"))
      (node (ref "OR1") (pin "7") (pinfunction "2_7") (pintype "passive"))
      (node (ref "OR7") (pin "7") (pinfunction "2_7") (pintype "passive"))
    )
    (net (code "43") (name "GPB6") (class "Default")
      (node (ref "IC1") (pin "7") (pinfunction "GPB6_7") (pintype "bidirectional"))
      (node (ref "OR1") (pin "6") (pinfunction "2_6") (pintype "passive"))
      (node (ref "OR7") (pin "6") (pinfunction "2_6") (pintype "passive"))
    )
    (net (code "44") (name "GPB7") (class "Default")
      (node (ref "IC1") (pin "8") (pinfunction "GPB7_8") (pintype "bidirectional"))
      (node (ref "OR1") (pin "5") (pinfunction "2_5") (pintype "passive"))
      (node (ref "OR7") (pin "5") (pinfunction "2_5") (pintype "passive"))
    )
    (net (code "45") (name "IO5") (class "Default")
      (node (ref "OK4") (pin "15") (pinfunction "EMIT_15") (pintype "passive"))
      (node (ref "OR6") (pin "1") (pinfunction "1_1") (pintype "passive"))
      (node (ref "U1") (pin "4") (pinfunction "4B_4") (pintype "input"))
    )
    (net (code "46") (name "IO6") (class "Default")
      (node (ref "OK4") (pin "13") (pinfunction "EMIT_13") (pintype "passive"))
      (node (ref "OR6") (pin "2") (pinfunction "1_2") (pintype "passive"))
      (node (ref "U1") (pin "3") (pinfunction "3B_3") (pintype "input"))
    )
    (net (code "47") (name "IO7") (class "Default")
      (node (ref "OK4") (pin "11") (pinfunction "EMIT_11") (pintype "passive"))
      (node (ref "OR6") (pin "3") (pinfunction "1_3") (pintype "passive"))
      (node (ref "U1") (pin "2") (pinfunction "2B_2") (pintype "input"))
    )
    (net (code "48") (name "IO8") (class "Default")
      (node (ref "OK4") (pin "9") (pinfunction "EMIT_9") (pintype "passive"))
      (node (ref "OR6") (pin "4") (pinfunction "1_4") (pintype "passive"))
      (node (ref "U1") (pin "1") (pinfunction "1B_1") (pintype "input"))
    )
    (net (code "49") (name "LEDA") (class "Default")
      (node (ref "ER3") (pin "1") (pinfunction "1_1") (pintype "passive"))
      (node (ref "ETHSOC") (pin "Y+") (pinfunction "Y+_Y+") (pintype "bidirectional"))
    )
    (net (code "50") (name "LEDB") (class "Default")
      (node (ref "ER4") (pin "1") (pinfunction "1_1") (pintype "passive"))
      (node (ref "ETHSOC") (pin "G+") (pinfunction "G+_G+") (pintype "bidirectional"))
    )
    (net (code "51") (name "Net-(ENC-LEDA)") (class "Default")
      (node (ref "ENC") (pin "27") (pinfunction "LEDA_27") (pintype "output"))
      (node (ref "ER3") (pin "2") (pinfunction "2_2") (pintype "passive"))
    )
    (net (code "52") (name "Net-(ENC-LEDB)") (class "Default")
      (node (ref "ENC") (pin "26") (pinfunction "LEDB_26") (pintype "output"))
      (node (ref "ER4") (pin "2") (pinfunction "2_2") (pintype "passive"))
    )
    (net (code "53") (name "Net-(ENC-OSC1)") (class "Default")
      (node (ref "EC1") (pin "1") (pinfunction "1_1") (pintype "passive"))
      (node (ref "ENC") (pin "23") (pinfunction "OSC1_23") (pintype "input"))
      (node (ref "Q2") (pin "2") (pinfunction "2_2") (pintype "passive"))
    )
    (net (code "54") (name "Net-(ENC-OSC2)") (class "Default")
      (node (ref "EC2") (pin "1") (pinfunction "1_1") (pintype "passive"))
      (node (ref "ENC") (pin "24") (pinfunction "OSC2_24") (pintype "output"))
      (node (ref "Q2") (pin "1") (pinfunction "1_1") (pintype "passive"))
    )
    (net (code "55") (name "Net-(ENC-RBIAS)") (class "Default")
      (node (ref "ENC") (pin "14") (pinfunction "RBIAS_14") (pintype "passive"))
      (node (ref "ER10") (pin "1") (pinfunction "1_1") (pintype "passive"))
    )
    (net (code "56") (name "Net-(ENC-RESET)") (class "Default")
      (node (ref "ENC") (pin "10") (pinfunction "RESET_10") (pintype "input"))
      (node (ref "ER1") (pin "1") (pinfunction "1_1") (pintype "passive"))
    )
    (net (code "57") (name "Net-(ENC-TPIN+)") (class "Default")
      (node (ref "ENC") (pin "13") (pinfunction "TPIN+_13") (pintype "input"))
      (node (ref "ERN1") (pin "6") (pinfunction "2_6") (pintype "passive"))
      (node (ref "ETHSOC") (pin "RD+") (pinfunction "RD+_RD+") (pintype "bidirectional"))
    )
    (net (code "58") (name "Net-(ENC-TPIN-)") (class "Default")
      (node (ref "ENC") (pin "12") (pinfunction "TPIN-_12") (pintype "input"))
      (node (ref "ERN1") (pin "5") (pinfunction "2_5") (pintype "passive"))
      (node (ref "ETHSOC") (pin "RD-") (pinfunction "RD-_RD-") (pintype "bidirectional"))
    )
    (net (code "59") (name "Net-(ENC-TPOUT+)") (class "Default")
      (node (ref "ENC") (pin "17") (pinfunction "TPOUT+_17") (pintype "output"))
      (node (ref "ERN1") (pin "1") (pinfunction "1_1") (pintype "passive"))
      (node (ref "ETHSOC") (pin "TD+") (pinfunction "TD+_TD+") (pintype "bidirectional"))
    )
    (net (code "60") (name "Net-(ENC-TPOUT-)") (class "Default")
      (node (ref "ENC") (pin "16") (pinfunction "TPOUT-_16") (pintype "output"))
      (node (ref "ERN1") (pin "2") (pinfunction "1_2") (pintype "passive"))
      (node (ref "ETHSOC") (pin "TD-") (pinfunction "TD-_TD-") (pintype "bidirectional"))
    )
    (net (code "61") (name "Net-(ENC-VCAP)") (class "Default")
      (node (ref "EC3") (pin "+") (pinfunction "+_+") (pintype "passive"))
      (node (ref "ENC") (pin "1") (pinfunction "VCAP_1") (pintype "power_in"))
    )
    (net (code "62") (name "Net-(ERN1A-2)") (class "Default")
      (node (ref "EC4") (pin "1") (pinfunction "1_1") (pintype "passive"))
      (node (ref "EL1") (pin "2") (pinfunction "2_2") (pintype "passive"))
      (node (ref "ERN1") (pin "7") (pinfunction "2_7") (pintype "passive"))
      (node (ref "ERN1") (pin "8") (pinfunction "2_8") (pintype "passive"))
      (node (ref "ETHSOC") (pin "P4") (pinfunction "P4_P4") (pintype "bidirectional"))
    )
    (net (code "63") (name "Net-(ERN1C-1)") (class "Default")
      (node (ref "EC5") (pin "1") (pinfunction "1_1") (pintype "passive"))
      (node (ref "ERN1") (pin "3") (pinfunction "1_3") (pintype "passive"))
      (node (ref "ERN1") (pin "4") (pinfunction "1_4") (pintype "passive"))
      (node (ref "ETHSOC") (pin "P5") (pinfunction "P5_P5") (pintype "bidirectional"))
    )
    (net (code "64") (name "Net-(IC1-A0)") (class "Default")
      (node (ref "IC1") (pin "15") (pinfunction "A0_15") (pintype "input"))
      (node (ref "MR3") (pin "1") (pinfunction "1_1") (pintype "passive"))
    )
    (net (code "65") (name "Net-(IIR1A-2)") (class "Default")
      (node (ref "IIR1") (pin "8") (pinfunction "2_8") (pintype "passive"))
      (node (ref "OK1") (pin "1") (pinfunction "A_1") (pintype "passive"))
    )
    (net (code "66") (name "Net-(IIR1B-1)") (class "Default")
      (node (ref "IIR1") (pin "2") (pinfunction "1_2") (pintype "passive"))
      (node (ref "XI1") (pin "3") (pinfunction "SK_3") (pintype "passive"))
    )
    (net (code "67") (name "Net-(IIR1B-2)") (class "Default")
      (node (ref "IIR1") (pin "7") (pinfunction "2_7") (pintype "passive"))
      (node (ref "OK1") (pin "3") (pinfunction "A_3") (pintype "passive"))
    )
    (net (code "68") (name "Net-(IIR1C-1)") (class "Default")
      (node (ref "IIR1") (pin "3") (pinfunction "1_3") (pintype "passive"))
      (node (ref "XI1") (pin "4") (pinfunction "SK_4") (pintype "passive"))
    )
    (net (code "69") (name "Net-(IIR1C-2)") (class "Default")
      (node (ref "IIR1") (pin "6") (pinfunction "2_6") (pintype "passive"))
      (node (ref "OK1") (pin "5") (pinfunction "A_5") (pintype "passive"))
    )
    (net (code "70") (name "Net-(IIR1D-1)") (class "Default")
      (node (ref "IIR1") (pin "4") (pinfunction "1_4") (pintype "passive"))
      (node (ref "XI1") (pin "5") (pinfunction "SK_5") (pintype "passive"))
    )
    (net (code "71") (name "Net-(IIR1D-2)") (class "Default")
      (node (ref "IIR1") (pin "5") (pinfunction "2_5") (pintype "passive"))
      (node (ref "OK1") (pin "7") (pinfunction "A_7") (pintype "passive"))
    )
    (net (code "72") (name "Net-(IIR2A-2)") (class "Default")
      (node (ref "IIR2") (pin "8") (pinfunction "2_8") (pintype "passive"))
      (node (ref "OK2") (pin "1") (pinfunction "A_1") (pintype "passive"))
    )
    (net (code "73") (name "Net-(IIR2B-1)") (class "Default")
      (node (ref "IIR2") (pin "2") (pinfunction "1_2") (pintype "passive"))
      (node (ref "XI2") (pin "3") (pinfunction "SK_3") (pintype "passive"))
    )
    (net (code "74") (name "Net-(IIR2B-2)") (class "Default")
      (node (ref "IIR2") (pin "7") (pinfunction "2_7") (pintype "passive"))
      (node (ref "OK2") (pin "3") (pinfunction "A_3") (pintype "passive"))
    )
    (net (code "75") (name "Net-(IIR2C-1)") (class "Default")
      (node (ref "IIR2") (pin "3") (pinfunction "1_3") (pintype "passive"))
      (node (ref "XI2") (pin "4") (pinfunction "SK_4") (pintype "passive"))
    )
    (net (code "76") (name "Net-(IIR2C-2)") (class "Default")
      (node (ref "IIR2") (pin "6") (pinfunction "2_6") (pintype "passive"))
      (node (ref "OK2") (pin "5") (pinfunction "A_5") (pintype "passive"))
    )
    (net (code "77") (name "Net-(IIR2D-1)") (class "Default")
      (node (ref "IIR2") (pin "4") (pinfunction "1_4") (pintype "passive"))
      (node (ref "XI2") (pin "5") (pinfunction "SK_5") (pintype "passive"))
    )
    (net (code "78") (name "Net-(IIR2D-2)") (class "Default")
      (node (ref "IIR2") (pin "5") (pinfunction "2_5") (pintype "passive"))
      (node (ref "OK2") (pin "7") (pinfunction "A_7") (pintype "passive"))
    )
    (net (code "79") (name "Net-(INDL-PadA)") (class "Default")
      (node (ref "INDL") (pin "A") (pinfunction "A_A") (pintype "passive"))
      (node (ref "R6") (pin "2") (pinfunction "2_2") (pintype "passive"))
    )
    (net (code "80") (name "Net-(IR3A-2)") (class "Default")
      (node (ref "IL1") (pin "C") (pinfunction "C_C") (pintype "passive"))
      (node (ref "IR3") (pin "8") (pinfunction "2_8") (pintype "passive"))
    )
    (net (code "81") (name "Net-(IR3B-2)") (class "Default")
      (node (ref "IL2") (pin "C") (pinfunction "C_C") (pintype "passive"))
      (node (ref "IR3") (pin "7") (pinfunction "2_7") (pintype "passive"))
    )
    (net (code "82") (name "Net-(IR3C-2)") (class "Default")
      (node (ref "IL3") (pin "C") (pinfunction "C_C") (pintype "passive"))
      (node (ref "IR3") (pin "6") (pinfunction "2_6") (pintype "passive"))
    )
    (net (code "83") (name "Net-(IR3D-2)") (class "Default")
      (node (ref "IL4") (pin "C") (pinfunction "C_C") (pintype "passive"))
      (node (ref "IR3") (pin "5") (pinfunction "2_5") (pintype "passive"))
    )
    (net (code "84") (name "Net-(IR4A-2)") (class "Default")
      (node (ref "IL5") (pin "C") (pinfunction "C_C") (pintype "passive"))
      (node (ref "IR4") (pin "8") (pinfunction "2_8") (pintype "passive"))
    )
    (net (code "85") (name "Net-(IR4B-2)") (class "Default")
      (node (ref "IL6") (pin "C") (pinfunction "C_C") (pintype "passive"))
      (node (ref "IR4") (pin "7") (pinfunction "2_7") (pintype "passive"))
    )
    (net (code "86") (name "Net-(IR4C-2)") (class "Default")
      (node (ref "IL7") (pin "C") (pinfunction "C_C") (pintype "passive"))
      (node (ref "IR4") (pin "6") (pinfunction "2_6") (pintype "passive"))
    )
    (net (code "87") (name "Net-(IR4D-2)") (class "Default")
      (node (ref "IL8") (pin "C") (pinfunction "C_C") (pintype "passive"))
      (node (ref "IR4") (pin "5") (pinfunction "2_5") (pintype "passive"))
    )
    (net (code "88") (name "Net-(MC-PB6(XTAL1{slash}TOSC1))") (class "Default")
      (node (ref "MC") (pin "7") (pinfunction "PB6(XTAL1/TOSC1)_7") (pintype "bidirectional"))
      (node (ref "Q1") (pin "1") (pinfunction "1_1") (pintype "passive"))
    )
    (net (code "89") (name "Net-(MC-PB7(XTAL2{slash}TOSC2))") (class "Default")
      (node (ref "MC") (pin "8") (pinfunction "PB7(XTAL2/TOSC2)_8") (pintype "bidirectional"))
      (node (ref "Q1") (pin "3") (pinfunction "3_3") (pintype "passive"))
    )
    (net (code "90") (name "Net-(OD1-PadC)") (class "Default")
      (node (ref "OD1") (pin "C") (pinfunction "C_C") (pintype "passive"))
      (node (ref "OMF") (pin "2") (pinfunction "2_2") (pintype "bidirectional"))
    )
    (net (code "91") (name "Net-(OK3A-A)") (class "Default")
      (node (ref "OK3") (pin "1") (pinfunction "A_1") (pintype "passive"))
      (node (ref "OR1") (pin "4") (pinfunction "1_4") (pintype "passive"))
    )
    (net (code "92") (name "Net-(OK3A-COL)") (class "Default")
      (node (ref "OK3") (pin "16") (pinfunction "COL_16") (pintype "passive"))
      (node (ref "OR3") (pin "1") (pinfunction "1_1") (pintype "passive"))
    )
    (net (code "93") (name "Net-(OK3B-A)") (class "Default")
      (node (ref "OK3") (pin "3") (pinfunction "A_3") (pintype "passive"))
      (node (ref "OR1") (pin "3") (pinfunction "1_3") (pintype "passive"))
    )
    (net (code "94") (name "Net-(OK3B-COL)") (class "Default")
      (node (ref "OK3") (pin "14") (pinfunction "COL_14") (pintype "passive"))
      (node (ref "OR3") (pin "2") (pinfunction "1_2") (pintype "passive"))
    )
    (net (code "95") (name "Net-(OK3C-A)") (class "Default")
      (node (ref "OK3") (pin "5") (pinfunction "A_5") (pintype "passive"))
      (node (ref "OR1") (pin "2") (pinfunction "1_2") (pintype "passive"))
    )
    (net (code "96") (name "Net-(OK3C-COL)") (class "Default")
      (node (ref "OK3") (pin "12") (pinfunction "COL_12") (pintype "passive"))
      (node (ref "OR3") (pin "3") (pinfunction "1_3") (pintype "passive"))
    )
    (net (code "97") (name "Net-(OK3D-A)") (class "Default")
      (node (ref "OK3") (pin "7") (pinfunction "A_7") (pintype "passive"))
      (node (ref "OR1") (pin "1") (pinfunction "1_1") (pintype "passive"))
    )
    (net (code "98") (name "Net-(OK3D-COL)") (class "Default")
      (node (ref "OK3") (pin "10") (pinfunction "COL_10") (pintype "passive"))
      (node (ref "OR3") (pin "4") (pinfunction "1_4") (pintype "passive"))
    )
    (net (code "99") (name "Net-(OK4A-A)") (class "Default")
      (node (ref "OK4") (pin "1") (pinfunction "A_1") (pintype "passive"))
      (node (ref "OR4") (pin "4") (pinfunction "1_4") (pintype "passive"))
    )
    (net (code "100") (name "Net-(OK4A-COL)") (class "Default")
      (node (ref "OK4") (pin "16") (pinfunction "COL_16") (pintype "passive"))
      (node (ref "OR5") (pin "1") (pinfunction "1_1") (pintype "passive"))
    )
    (net (code "101") (name "Net-(OK4B-A)") (class "Default")
      (node (ref "OK4") (pin "3") (pinfunction "A_3") (pintype "passive"))
      (node (ref "OR4") (pin "3") (pinfunction "1_3") (pintype "passive"))
    )
    (net (code "102") (name "Net-(OK4B-COL)") (class "Default")
      (node (ref "OK4") (pin "14") (pinfunction "COL_14") (pintype "passive"))
      (node (ref "OR5") (pin "2") (pinfunction "1_2") (pintype "passive"))
    )
    (net (code "103") (name "Net-(OK4C-A)") (class "Default")
      (node (ref "OK4") (pin "5") (pinfunction "A_5") (pintype "passive"))
      (node (ref "OR4") (pin "2") (pinfunction "1_2") (pintype "passive"))
    )
    (net (code "104") (name "Net-(OK4C-COL)") (class "Default")
      (node (ref "OK4") (pin "12") (pinfunction "COL_12") (pintype "passive"))
      (node (ref "OR5") (pin "3") (pinfunction "1_3") (pintype "passive"))
    )
    (net (code "105") (name "Net-(OK4D-A)") (class "Default")
      (node (ref "OK4") (pin "7") (pinfunction "A_7") (pintype "passive"))
      (node (ref "OR4") (pin "1") (pinfunction "1_1") (pintype "passive"))
    )
    (net (code "106") (name "Net-(OK4D-COL)") (class "Default")
      (node (ref "OK4") (pin "10") (pinfunction "COL_10") (pintype "passive"))
      (node (ref "OR5") (pin "4") (pinfunction "1_4") (pintype "passive"))
    )
    (net (code "107") (name "Net-(OL4-PadA)") (class "Default")
      (node (ref "OL4") (pin "A") (pinfunction "A_A") (pintype "passive"))
      (node (ref "OR7") (pin "1") (pinfunction "1_1") (pintype "passive"))
    )
    (net (code "108") (name "Net-(OL8-PadA)") (class "Default")
      (node (ref "OL8") (pin "A") (pinfunction "A_A") (pintype "passive"))
      (node (ref "OR8") (pin "1") (pinfunction "1_1") (pintype "passive"))
    )
    (net (code "109") (name "Net-(OR7B-1)") (class "Default")
      (node (ref "OL3") (pin "A") (pinfunction "A_A") (pintype "passive"))
      (node (ref "OR7") (pin "2") (pinfunction "1_2") (pintype "passive"))
    )
    (net (code "110") (name "Net-(OR7C-1)") (class "Default")
      (node (ref "OL2") (pin "A") (pinfunction "A_A") (pintype "passive"))
      (node (ref "OR7") (pin "3") (pinfunction "1_3") (pintype "passive"))
    )
    (net (code "111") (name "Net-(OR7D-1)") (class "Default")
      (node (ref "OL1") (pin "A") (pinfunction "A_A") (pintype "passive"))
      (node (ref "OR7") (pin "4") (pinfunction "1_4") (pintype "passive"))
    )
    (net (code "112") (name "Net-(OR8B-1)") (class "Default")
      (node (ref "OL7") (pin "A") (pinfunction "A_A") (pintype "passive"))
      (node (ref "OR8") (pin "2") (pinfunction "1_2") (pintype "passive"))
    )
    (net (code "113") (name "Net-(OR8C-1)") (class "Default")
      (node (ref "OL6") (pin "A") (pinfunction "A_A") (pintype "passive"))
      (node (ref "OR8") (pin "3") (pinfunction "1_3") (pintype "passive"))
    )
    (net (code "114") (name "Net-(OR8D-1)") (class "Default")
      (node (ref "OL5") (pin "A") (pinfunction "A_A") (pintype "passive"))
      (node (ref "OR8") (pin "4") (pinfunction "1_4") (pintype "passive"))
    )
    (net (code "115") (name "Net-(PD1-PadC)") (class "Default")
      (node (ref "PD1") (pin "C") (pinfunction "C_C") (pintype "passive"))
      (node (ref "PF1") (pin "1") (pinfunction "1_1") (pintype "passive"))
    )
    (net (code "116") (name "Net-(PIC33-OUT)") (class "Default")
      (node (ref "PCO") (pin "P$2") (pinfunction "P$2_P$2") (pintype "passive"))
      (node (ref "PD2") (pin "C") (pinfunction "C_C") (pintype "passive"))
      (node (ref "PIC33") (pin "2") (pinfunction "OUT_2") (pintype "output"))
    )
    (net (code "117") (name "Net-(PL-PadA)") (class "Default")
      (node (ref "PL") (pin "A") (pinfunction "A_A") (pintype "passive"))
      (node (ref "PR1") (pin "1") (pinfunction "1_1") (pintype "passive"))
    )
    (net (code "118") (name "Net-(U1-1C)") (class "Default")
      (node (ref "D1") (pin "2") (pinfunction "2_2") (pintype "bidirectional"))
      (node (ref "OF8") (pin "2") (pinfunction "2_2") (pintype "bidirectional"))
      (node (ref "U1") (pin "18") (pinfunction "1C_18") (pintype "output"))
    )
    (net (code "119") (name "Net-(U1-2C)") (class "Default")
      (node (ref "D1") (pin "1") (pinfunction "1_1") (pintype "bidirectional"))
      (node (ref "OF7") (pin "2") (pinfunction "2_2") (pintype "bidirectional"))
      (node (ref "U1") (pin "17") (pinfunction "2C_17") (pintype "output"))
    )
    (net (code "120") (name "Net-(U1-3C)") (class "Default")
      (node (ref "D2") (pin "2") (pinfunction "2_2") (pintype "bidirectional"))
      (node (ref "OF6") (pin "2") (pinfunction "2_2") (pintype "bidirectional"))
      (node (ref "U1") (pin "16") (pinfunction "3C_16") (pintype "output"))
    )
    (net (code "121") (name "Net-(U1-4C)") (class "Default")
      (node (ref "D2") (pin "1") (pinfunction "1_1") (pintype "bidirectional"))
      (node (ref "OF5") (pin "2") (pinfunction "2_2") (pintype "bidirectional"))
      (node (ref "U1") (pin "15") (pinfunction "4C_15") (pintype "output"))
    )
    (net (code "122") (name "Net-(U1-5C)") (class "Default")
      (node (ref "D3") (pin "2") (pinfunction "2_2") (pintype "bidirectional"))
      (node (ref "OF4") (pin "2") (pinfunction "2_2") (pintype "bidirectional"))
      (node (ref "U1") (pin "14") (pinfunction "5C_14") (pintype "output"))
    )
    (net (code "123") (name "Net-(U1-6C)") (class "Default")
      (node (ref "D3") (pin "1") (pinfunction "1_1") (pintype "bidirectional"))
      (node (ref "OF3") (pin "2") (pinfunction "2_2") (pintype "bidirectional"))
      (node (ref "U1") (pin "13") (pinfunction "6C_13") (pintype "output"))
    )
    (net (code "124") (name "Net-(U1-7C)") (class "Default")
      (node (ref "D4") (pin "2") (pinfunction "2_2") (pintype "bidirectional"))
      (node (ref "OF2") (pin "2") (pinfunction "2_2") (pintype "bidirectional"))
      (node (ref "U1") (pin "12") (pinfunction "7C_12") (pintype "output"))
    )
    (net (code "125") (name "Net-(U1-8C)") (class "Default")
      (node (ref "D4") (pin "1") (pinfunction "1_1") (pintype "bidirectional"))
      (node (ref "OF1") (pin "2") (pinfunction "2_2") (pintype "bidirectional"))
      (node (ref "U1") (pin "11") (pinfunction "8C_11") (pintype "output"))
    )
    (net (code "126") (name "Net-(XI1B-SK)") (class "Default")
      (node (ref "IIR1") (pin "1") (pinfunction "1_1") (pintype "passive"))
      (node (ref "XI1") (pin "2") (pinfunction "SK_2") (pintype "passive"))
    )
    (net (code "127") (name "Net-(XI2B-SK)") (class "Default")
      (node (ref "IIR2") (pin "1") (pinfunction "1_1") (pintype "passive"))
      (node (ref "XI2") (pin "2") (pinfunction "SK_2") (pintype "passive"))
    )
    (net (code "128") (name "Net-(XOA-SK)") (class "Default")
      (node (ref "OD1") (pin "A") (pinfunction "A_A") (pintype "passive"))
      (node (ref "XO") (pin "1") (pinfunction "SK_1") (pintype "passive"))
    )
    (net (code "129") (name "Net-(XOB-SK)") (class "Default")
      (node (ref "OF8") (pin "1") (pinfunction "1_1") (pintype "bidirectional"))
      (node (ref "XO") (pin "10") (pinfunction "SK_10") (pintype "passive"))
    )
    (net (code "130") (name "Net-(XOD-SK)") (class "Default")
      (node (ref "OF1") (pin "1") (pinfunction "1_1") (pintype "bidirectional"))
      (node (ref "XO") (pin "3") (pinfunction "SK_3") (pintype "passive"))
    )
    (net (code "131") (name "Net-(XOE-SK)") (class "Default")
      (node (ref "OF2") (pin "1") (pinfunction "1_1") (pintype "bidirectional"))
      (node (ref "XO") (pin "4") (pinfunction "SK_4") (pintype "passive"))
    )
    (net (code "132") (name "Net-(XOF-SK)") (class "Default")
      (node (ref "OF3") (pin "1") (pinfunction "1_1") (pintype "bidirectional"))
      (node (ref "XO") (pin "5") (pinfunction "SK_5") (pintype "passive"))
    )
    (net (code "133") (name "Net-(XOG-SK)") (class "Default")
      (node (ref "OF4") (pin "1") (pinfunction "1_1") (pintype "bidirectional"))
      (node (ref "XO") (pin "6") (pinfunction "SK_6") (pintype "passive"))
    )
    (net (code "134") (name "Net-(XOH-SK)") (class "Default")
      (node (ref "OF5") (pin "1") (pinfunction "1_1") (pintype "bidirectional"))
      (node (ref "XO") (pin "7") (pinfunction "SK_7") (pintype "passive"))
    )
    (net (code "135") (name "Net-(XOI-SK)") (class "Default")
      (node (ref "OF6") (pin "1") (pinfunction "1_1") (pintype "bidirectional"))
      (node (ref "XO") (pin "8") (pinfunction "SK_8") (pintype "passive"))
    )
    (net (code "136") (name "Net-(XOJ-SK)") (class "Default")
      (node (ref "OF7") (pin "1") (pinfunction "1_1") (pintype "bidirectional"))
      (node (ref "XO") (pin "9") (pinfunction "SK_9") (pintype "passive"))
    )
    (net (code "137") (name "OI1") (class "Default")
      (node (ref "OK3") (pin "15") (pinfunction "EMIT_15") (pintype "passive"))
      (node (ref "OR2") (pin "1") (pinfunction "1_1") (pintype "passive"))
      (node (ref "U1") (pin "8") (pinfunction "8B_8") (pintype "input"))
    )
    (net (code "138") (name "OI2") (class "Default")
      (node (ref "OK3") (pin "13") (pinfunction "EMIT_13") (pintype "passive"))
      (node (ref "OR2") (pin "2") (pinfunction "1_2") (pintype "passive"))
      (node (ref "U1") (pin "7") (pinfunction "7B_7") (pintype "input"))
    )
    (net (code "139") (name "OI3") (class "Default")
      (node (ref "OK3") (pin "11") (pinfunction "EMIT_11") (pintype "passive"))
      (node (ref "OR2") (pin "3") (pinfunction "1_3") (pintype "passive"))
      (node (ref "U1") (pin "6") (pinfunction "6B_6") (pintype "input"))
    )
    (net (code "140") (name "OI4") (class "Default")
      (node (ref "OK3") (pin "9") (pinfunction "EMIT_9") (pintype "passive"))
      (node (ref "OR2") (pin "4") (pinfunction "1_4") (pintype "passive"))
      (node (ref "U1") (pin "5") (pinfunction "5B_5") (pintype "input"))
    )
    (net (code "141") (name "RAW_IV") (class "Default")
      (node (ref "GPIO") (pin "1") (pinfunction "S_1") (pintype "passive"))
      (node (ref "PC1") (pin "+") (pinfunction "+_+") (pintype "passive"))
      (node (ref "PF1") (pin "2") (pinfunction "2_2") (pintype "passive"))
      (node (ref "PIC33") (pin "1") (pinfunction "VIN_1") (pintype "input"))
    )
    (net (code "142") (name "RESET") (class "Default")
      (node (ref "BL") (pin "5") (pinfunction "S_5") (pintype "passive"))
      (node (ref "C2") (pin "1") (pinfunction "1_1") (pintype "passive"))
      (node (ref "MC") (pin "29") (pinfunction "PC6(/RESET)_29") (pintype "bidirectional"))
      (node (ref "R2") (pin "1") (pinfunction "1_1") (pintype "passive"))
      (node (ref "SR") (pin "1") (pinfunction "P_1") (pintype "passive"))
    )
    (net (code "143") (name "RXI") (class "Default")
      (node (ref "MC") (pin "30") (pinfunction "PD0(RXD)_30") (pintype "bidirectional"))
      (node (ref "PP") (pin "4") (pinfunction "S_4") (pintype "passive"))
    )
    (net (code "144") (name "TXO") (class "Default")
      (node (ref "MC") (pin "31") (pinfunction "PD1(TXD)_31") (pintype "bidirectional"))
      (node (ref "PP") (pin "3") (pinfunction "S_3") (pintype "passive"))
    )
    (net (code "145") (name "VDDO") (class "Default")
      (node (ref "D1") (pin "3") (pinfunction "3_3") (pintype "bidirectional"))
      (node (ref "D2") (pin "3") (pinfunction "3_3") (pintype "bidirectional"))
      (node (ref "D3") (pin "3") (pinfunction "3_3") (pintype "bidirectional"))
      (node (ref "D4") (pin "3") (pinfunction "3_3") (pintype "bidirectional"))
      (node (ref "EC6") (pin "+") (pinfunction "+_+") (pintype "passive"))
      (node (ref "OD2") (pin "C") (pinfunction "C_C") (pintype "passive"))
      (node (ref "OMF") (pin "1") (pinfunction "1_1") (pintype "bidirectional"))
      (node (ref "OR3") (pin "5") (pinfunction "2_5") (pintype "passive"))
      (node (ref "OR3") (pin "6") (pinfunction "2_6") (pintype "passive"))
      (node (ref "OR3") (pin "7") (pinfunction "2_7") (pintype "passive"))
      (node (ref "OR3") (pin "8") (pinfunction "2_8") (pintype "passive"))
      (node (ref "OR5") (pin "5") (pinfunction "2_5") (pintype "passive"))
      (node (ref "OR5") (pin "6") (pinfunction "2_6") (pintype "passive"))
      (node (ref "OR5") (pin "7") (pinfunction "2_7") (pintype "passive"))
      (node (ref "OR5") (pin "8") (pinfunction "2_8") (pintype "passive"))
      (node (ref "U1") (pin "10") (pinfunction "COM_10") (pintype "output"))
    )
    (net (code "146") (name "VIN") (class "Default")
      (node (ref "PD1") (pin "A") (pinfunction "A_A") (pintype "passive"))
      (node (ref "PJ1") (pin "VIN0") (pinfunction "PWR_VIN0") (pintype "bidirectional"))
      (node (ref "XV") (pin "2") (pinfunction "SK_2") (pintype "passive"))
    )
    (net (code "147") (name "WFGPIO0") (class "Default")
      (node (ref "GPIO") (pin "13") (pinfunction "S_13") (pintype "passive"))
      (node (ref "WIFI") (pin "GPIO0") (pinfunction "GPIO0_GPIO0") (pintype "bidirectional"))
    )
    (net (code "148") (name "WFGPIO2") (class "Default")
      (node (ref "GPIO") (pin "14") (pinfunction "S_14") (pintype "passive"))
      (node (ref "WIFI") (pin "GPIO2") (pinfunction "GPIO2_GPIO2") (pintype "bidirectional"))
    )
    (net (code "149") (name "unconnected-(ENC-CLKOUT-Pad3)") (class "Default")
      (node (ref "ENC") (pin "3") (pinfunction "CLKOUT_3") (pintype "output"))
    )
    (net (code "150") (name "unconnected-(ENC-WOL-Pad5)") (class "Default")
      (node (ref "ENC") (pin "5") (pinfunction "WOL_5") (pintype "output"))
    )
    (net (code "151") (name "unconnected-(ETHSOC-PadNC)") (class "Default")
      (node (ref "ETHSOC") (pin "NC") (pinfunction "NC_NC") (pintype "bidirectional"))
    )
    (net (code "152") (name "unconnected-(IC1-INTA-Pad20)") (class "Default")
      (node (ref "IC1") (pin "20") (pinfunction "INTA_20") (pintype "output"))
    )
    (net (code "153") (name "unconnected-(PJ1-GND-PadP$4)") (class "Default")
      (node (ref "PJ1") (pin "P$4") (pinfunction "GND_P$4") (pintype "bidirectional"))
    )
    (net (code "154") (name "unconnected-(SHT-PadALERT)") (class "Default")
      (node (ref "SHT") (pin "ALERT") (pinfunction "ALERT_ALERT") (pintype "bidirectional"))
    )
    (net (code "155") (name "unconnected-(SHT-PadRESET)") (class "Default")
      (node (ref "SHT") (pin "RESET") (pinfunction "RESET_RESET") (pintype "bidirectional"))
    )
    (net (code "156") (name "unconnected-(WIFI-PadRST)") (class "Default")
      (node (ref "WIFI") (pin "RST") (pinfunction "RST_RST") (pintype "bidirectional"))
    )
  )
)
